# MD2020_02-08.net
KiCad netlist of a schematic drawn in EAGLE
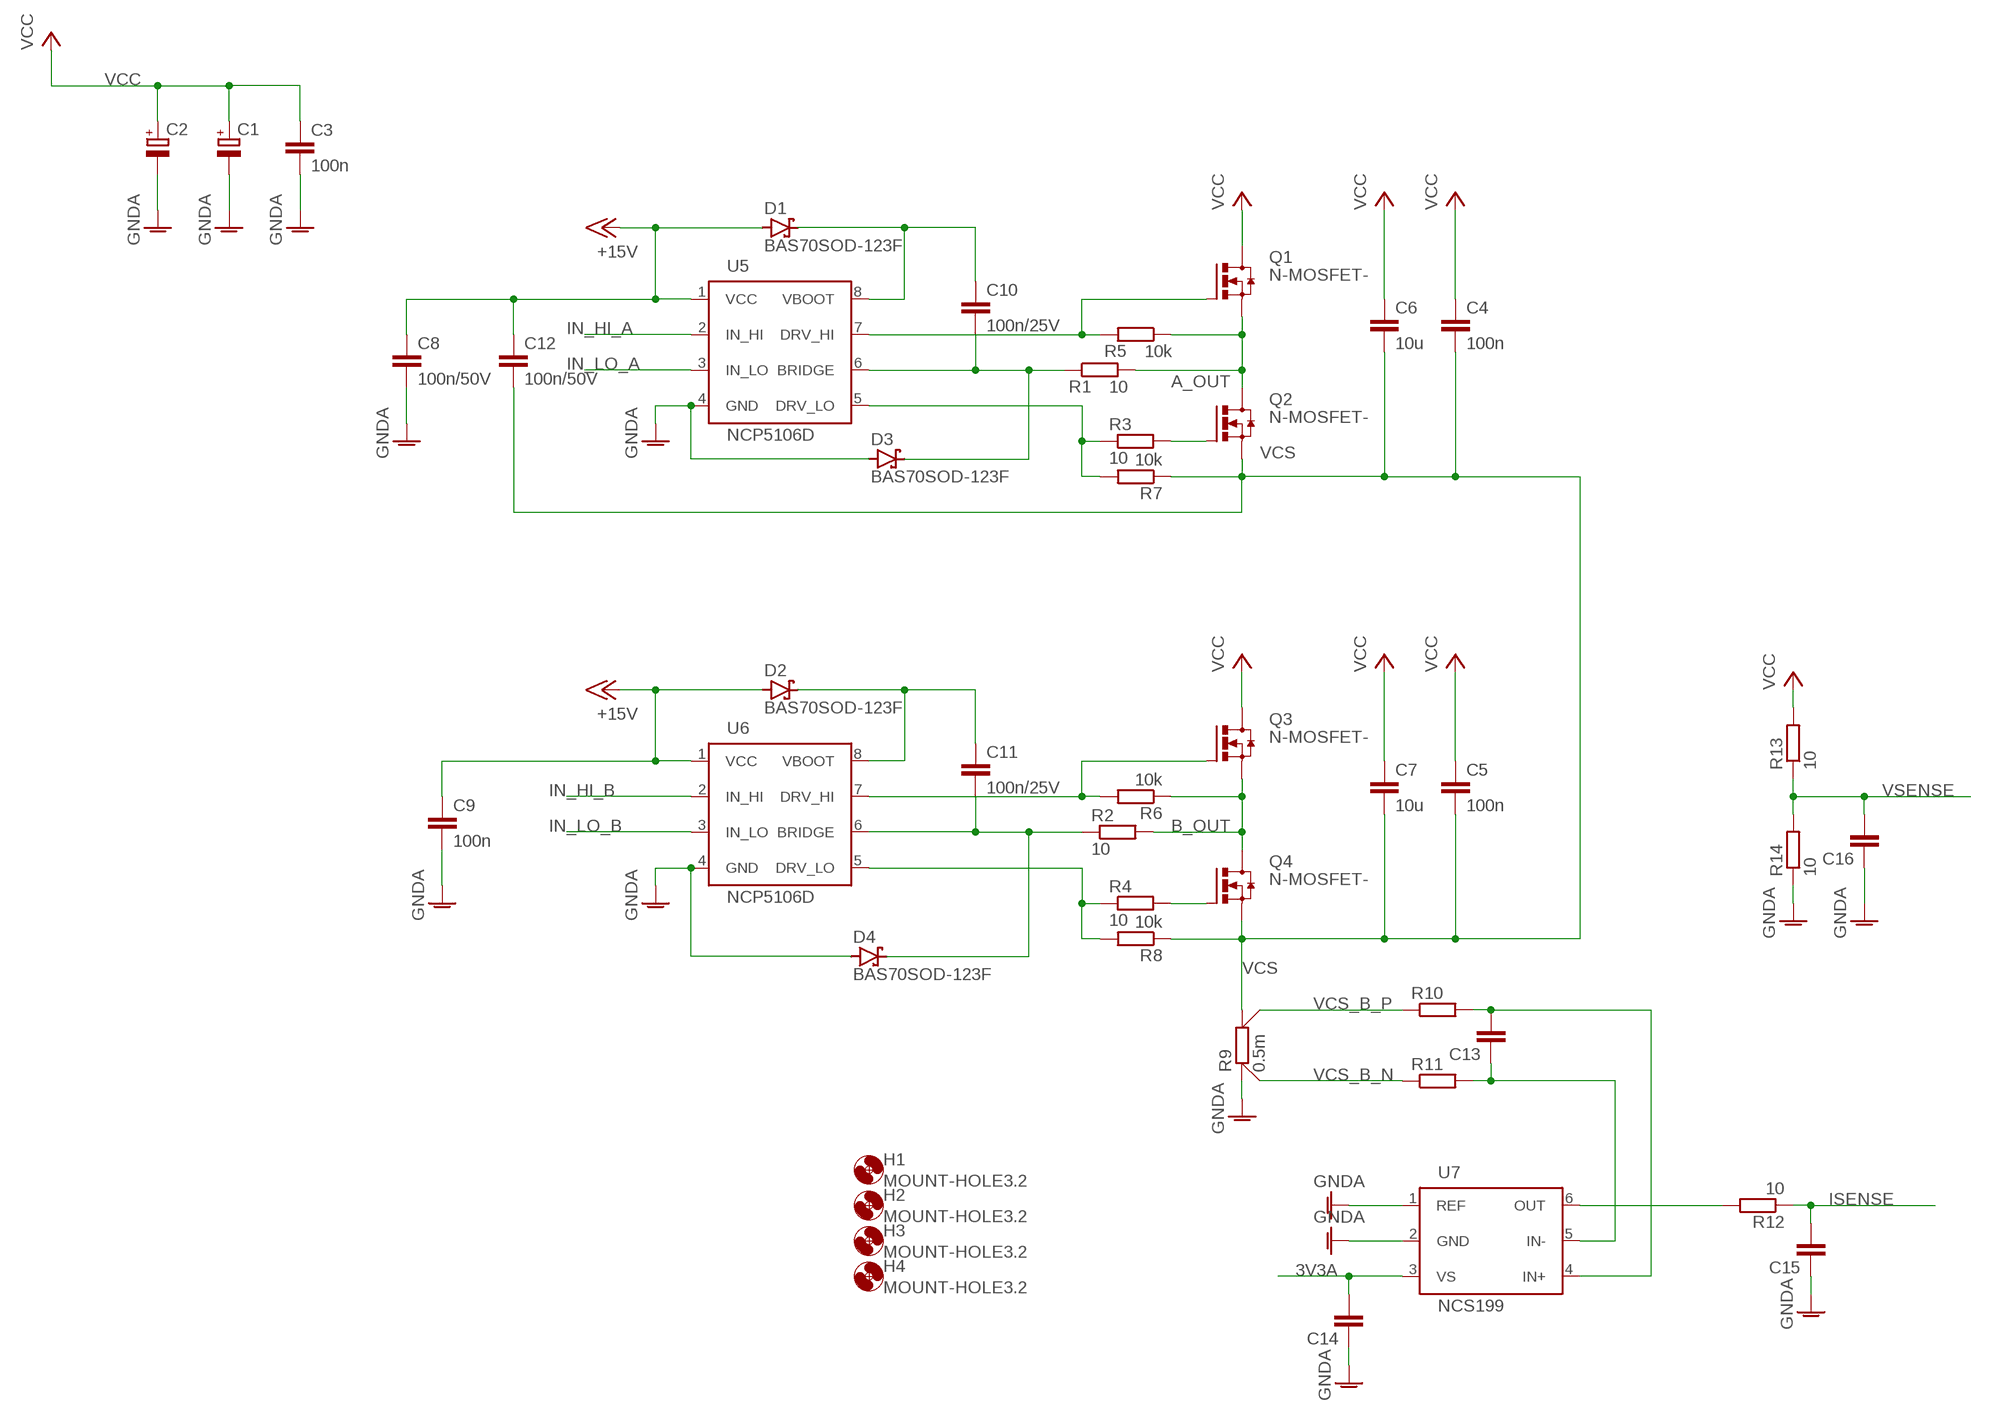
[diagram p0: schematic, sheet 1]
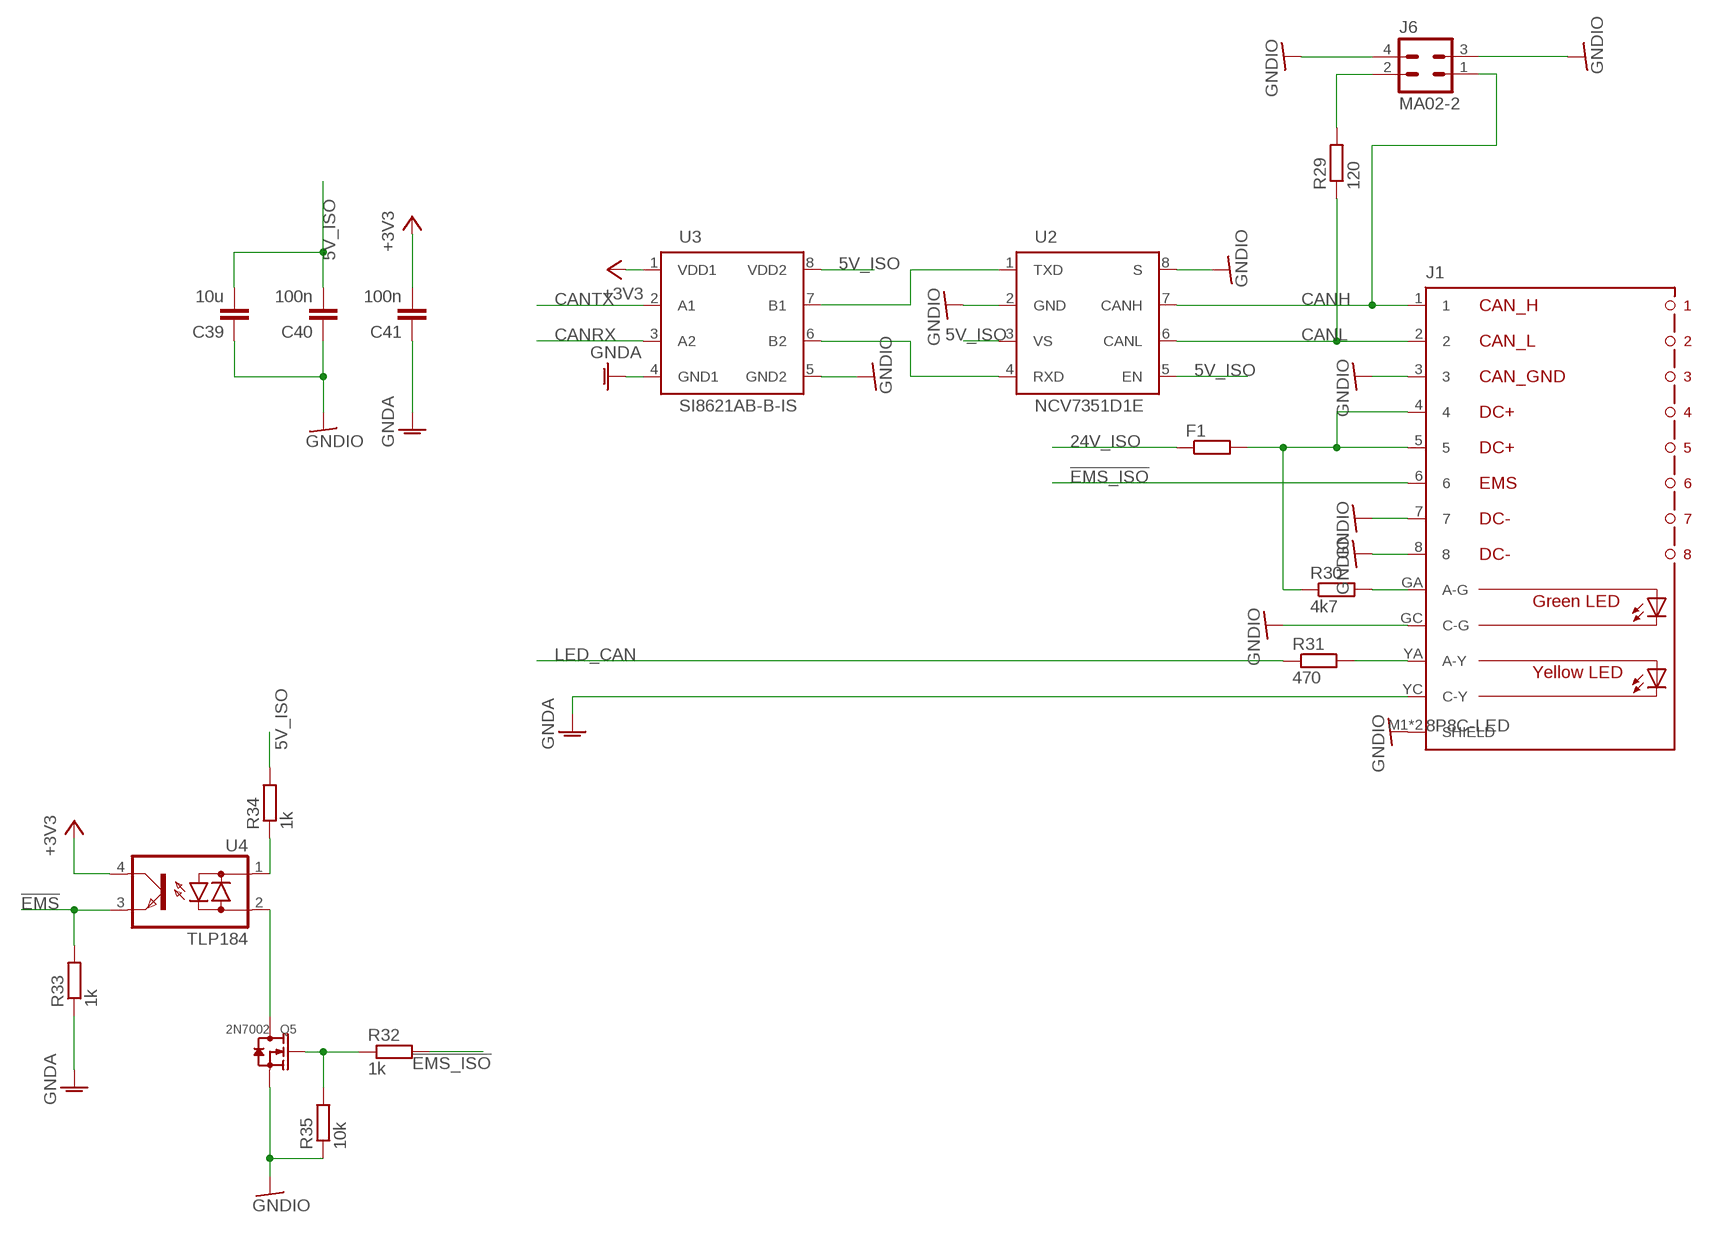
[diagram p1: schematic, sheet 2]
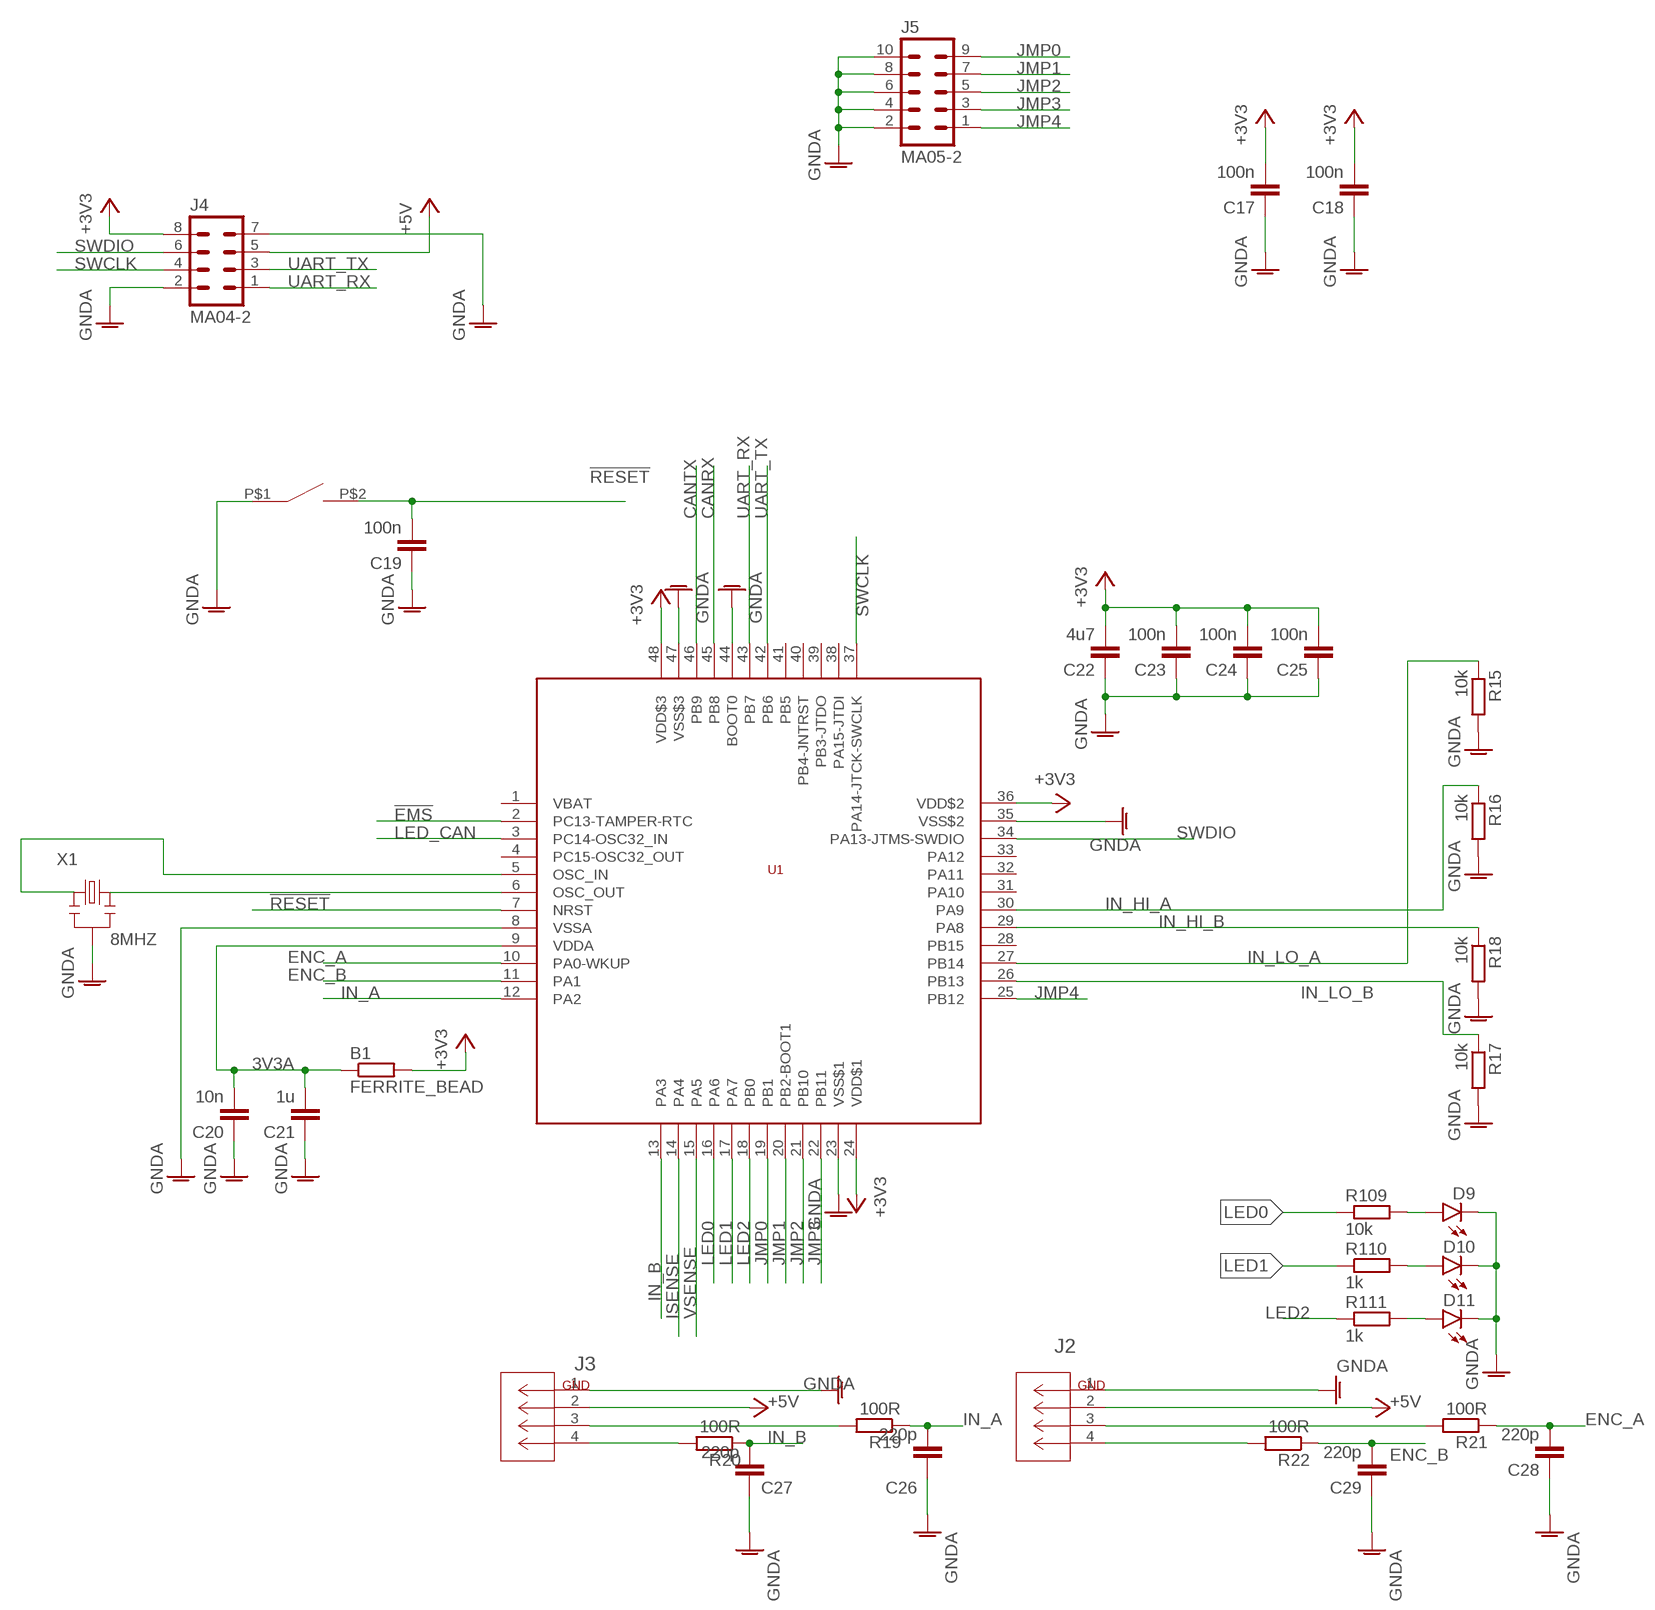
[diagram p2: schematic, sheet 3]
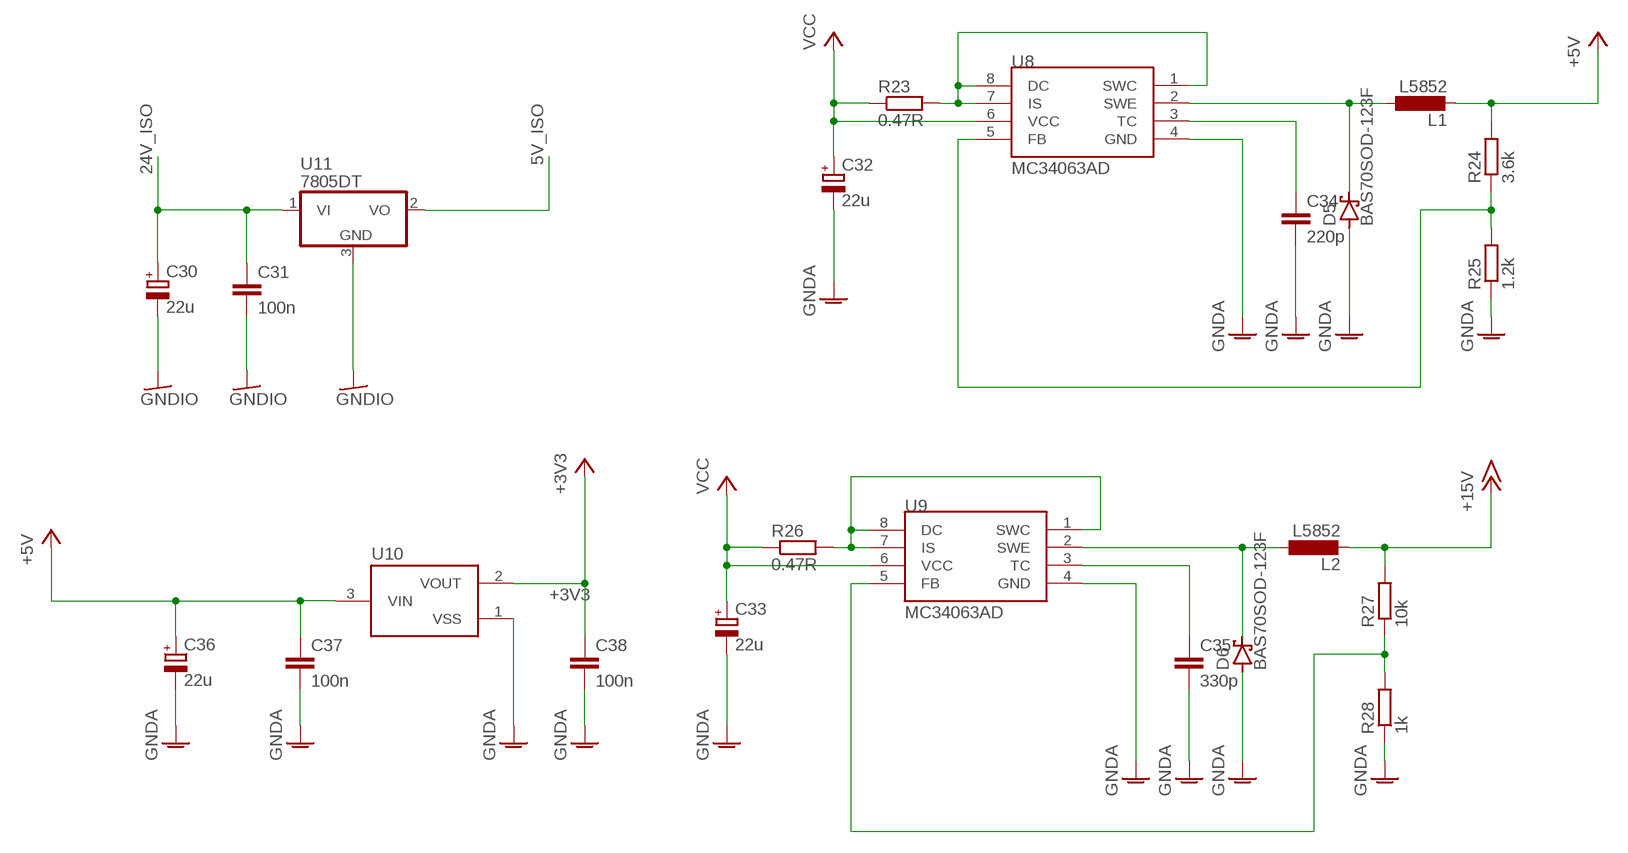
[diagram p3: schematic, sheet 4]

(export (version "E")
  (design (tool "Eeschema 10.0.6"))
  (components
    (comp (ref "C1")
      (value "CPOL-EUE5-10.5")
      (footprint "eagle-import:E5-10,5")
      (libsource (lib "eagle-import") (part "CPOL-EUE5-10.5"))
    )
    (comp (ref "C2")
      (value "CPOL-EUE5-10.5")
      (footprint "eagle-import:E5-10,5")
      (libsource (lib "eagle-import") (part "CPOL-EUE5-10.5"))
    )
    (comp (ref "C3")
      (value "100n")
      (footprint "eagle-import:C0603")
      (fields (field (name "MPN") "CC0603KRX7R9BB104 "))
      (libsource (lib "eagle-import") (part "C-EUC0603"))
    )
    (comp (ref "C4")
      (value "100n")
      (footprint "eagle-import:C0603")
      (fields (field (name "MPN") "CC0603KRX7R9BB104 "))
      (libsource (lib "eagle-import") (part "C-EUC0603"))
    )
    (comp (ref "C5")
      (value "100n")
      (footprint "eagle-import:C0603")
      (fields (field (name "MPN") "CC0603KRX7R9BB104 "))
      (libsource (lib "eagle-import") (part "C-EUC0603"))
    )
    (comp (ref "C6")
      (value "10u")
      (footprint "eagle-import:C1210")
      (fields (field (name "MPN") "CL31A106KBHNNNE "))
      (libsource (lib "eagle-import") (part "C-EUC1210"))
    )
    (comp (ref "C7")
      (value "10u")
      (footprint "eagle-import:C1210")
      (fields (field (name "MPN") "CL31A106KBHNNNE "))
      (libsource (lib "eagle-import") (part "C-EUC1210"))
    )
    (comp (ref "C8")
      (value "100n/50V")
      (footprint "eagle-import:C0603")
      (fields (field (name "MPN") "CC0603KRX7R9BB104 "))
      (libsource (lib "eagle-import") (part "C-EUC0603"))
    )
    (comp (ref "C9")
      (value "100n")
      (footprint "eagle-import:C0603")
      (fields (field (name "MPN") "CC0603KRX7R9BB104 "))
      (libsource (lib "eagle-import") (part "C-EUC0603"))
    )
    (comp (ref "C10")
      (value "100n/25V")
      (footprint "eagle-import:C0603")
      (fields (field (name "MPN") "CC0603KRX7R9BB104 "))
      (libsource (lib "eagle-import") (part "C-EUC0603"))
    )
    (comp (ref "C11")
      (value "100n/25V")
      (footprint "eagle-import:C0603")
      (fields (field (name "MPN") "CC0603KRX7R9BB104 "))
      (libsource (lib "eagle-import") (part "C-EUC0603"))
    )
    (comp (ref "C12")
      (value "100n/50V")
      (footprint "eagle-import:C0603")
      (fields (field (name "MPN") "CC0603KRX7R9BB104 "))
      (libsource (lib "eagle-import") (part "C-EUC0603"))
    )
    (comp (ref "C13")
      (value "C-EUC0603")
      (footprint "eagle-import:C0603")
      (libsource (lib "eagle-import") (part "rcl_334_C-EUC0603"))
    )
    (comp (ref "C14")
      (value "C-EUC0603")
      (footprint "eagle-import:C0603")
      (libsource (lib "eagle-import") (part "rcl_334_C-EUC0603"))
    )
    (comp (ref "C15")
      (value "C-EUC0603")
      (footprint "eagle-import:C0603")
      (libsource (lib "eagle-import") (part "rcl_334_C-EUC0603"))
    )
    (comp (ref "C16")
      (value "C-EUC0603")
      (footprint "eagle-import:C0603")
      (libsource (lib "eagle-import") (part "rcl_334_C-EUC0603"))
    )
    (comp (ref "D1")
      (value "BAS70SOD-123F")
      (footprint "eagle-import:SOD123F")
      (fields (field (name "MPN") "PMEG4010EH,115"))
      (libsource (lib "eagle-import") (part "BAS70SOD-123F"))
    )
    (comp (ref "D2")
      (value "BAS70SOD-123F")
      (footprint "eagle-import:SOD123F")
      (fields (field (name "MPN") "PMEG4010EH,115"))
      (libsource (lib "eagle-import") (part "BAS70SOD-123F"))
    )
    (comp (ref "D3")
      (value "BAS70SOD-123F")
      (footprint "eagle-import:SOD123F")
      (fields (field (name "MPN") "PMEG4010EH,115"))
      (libsource (lib "eagle-import") (part "BAS70SOD-123F"))
    )
    (comp (ref "D4")
      (value "BAS70SOD-123F")
      (footprint "eagle-import:SOD123F")
      (fields (field (name "MPN") "PMEG4010EH,115"))
      (libsource (lib "eagle-import") (part "BAS70SOD-123F"))
    )
    (comp (ref "H1")
      (value "MOUNT-HOLE3.2")
      (footprint "eagle-import:3,2")
      (libsource (lib "eagle-import") (part "MOUNT-HOLE3.2"))
    )
    (comp (ref "H2")
      (value "MOUNT-HOLE3.2")
      (footprint "eagle-import:3,2")
      (libsource (lib "eagle-import") (part "MOUNT-HOLE3.2"))
    )
    (comp (ref "H3")
      (value "MOUNT-HOLE3.2")
      (footprint "eagle-import:3,2")
      (libsource (lib "eagle-import") (part "MOUNT-HOLE3.2"))
    )
    (comp (ref "H4")
      (value "MOUNT-HOLE3.2")
      (footprint "eagle-import:3,2")
      (libsource (lib "eagle-import") (part "MOUNT-HOLE3.2"))
    )
    (comp (ref "Q1")
      (value "N-MOSFET-")
      (footprint "eagle-import:SOT669")
      (libsource (lib "eagle-import") (part "N-MOSFET-"))
    )
    (comp (ref "Q2")
      (value "N-MOSFET-")
      (footprint "eagle-import:SOT669")
      (libsource (lib "eagle-import") (part "N-MOSFET-"))
    )
    (comp (ref "Q3")
      (value "N-MOSFET-")
      (footprint "eagle-import:SOT669")
      (libsource (lib "eagle-import") (part "N-MOSFET-"))
    )
    (comp (ref "Q4")
      (value "N-MOSFET-")
      (footprint "eagle-import:SOT669")
      (libsource (lib "eagle-import") (part "N-MOSFET-"))
    )
    (comp (ref "R1")
      (value "10")
      (footprint "eagle-import:R0603")
      (fields (field (name "MPN") "RC0603FR-0710RL"))
      (libsource (lib "eagle-import") (part "R-EU_R0603"))
    )
    (comp (ref "R2")
      (value "10")
      (footprint "eagle-import:R0603")
      (fields (field (name "MPN") "RC0603FR-0710RL"))
      (libsource (lib "eagle-import") (part "R-EU_R0603"))
    )
    (comp (ref "R3")
      (value "10")
      (footprint "eagle-import:R0603")
      (fields (field (name "MPN") "RC0603FR-0710RL"))
      (libsource (lib "eagle-import") (part "R-EU_R0603"))
    )
    (comp (ref "R4")
      (value "10")
      (footprint "eagle-import:R0603")
      (fields (field (name "MPN") "RC0603FR-0710RL"))
      (libsource (lib "eagle-import") (part "R-EU_R0603"))
    )
    (comp (ref "R5")
      (value "10k")
      (footprint "eagle-import:R0603")
      (fields (field (name "MPN") "RC0603FR-0710KL "))
      (libsource (lib "eagle-import") (part "R-EU_R0603"))
    )
    (comp (ref "R6")
      (value "10k")
      (footprint "eagle-import:R0603")
      (fields (field (name "MPN") "RC0603FR-0710KL "))
      (libsource (lib "eagle-import") (part "R-EU_R0603"))
    )
    (comp (ref "R7")
      (value "10k")
      (footprint "eagle-import:R0603")
      (fields (field (name "MPN") "RC0603FR-0710KL "))
      (libsource (lib "eagle-import") (part "R-EU_R0603"))
    )
    (comp (ref "R8")
      (value "10k")
      (footprint "eagle-import:R0603")
      (fields (field (name "MPN") "RC0603FR-0710KL "))
      (libsource (lib "eagle-import") (part "R-EU_R0603"))
    )
    (comp (ref "R9")
      (value "0.5m")
      (footprint "eagle-import:CSS2H-2512")
      (libsource (lib "eagle-import") (part "CSS2H-2512"))
    )
    (comp (ref "R10")
      (value "R-EU_R0603")
      (footprint "eagle-import:R0603")
      (libsource (lib "eagle-import") (part "rcl_334_R-EU_R0603"))
    )
    (comp (ref "R11")
      (value "R-EU_R0603")
      (footprint "eagle-import:R0603")
      (libsource (lib "eagle-import") (part "rcl_334_R-EU_R0603"))
    )
    (comp (ref "R12")
      (value "10")
      (footprint "eagle-import:R0603")
      (fields (field (name "MPN") "RC0603FR-0710RL"))
      (libsource (lib "eagle-import") (part "R-EU_R0603"))
    )
    (comp (ref "R13")
      (value "10")
      (footprint "eagle-import:R0603")
      (fields (field (name "MPN") "RC0603FR-0710RL"))
      (libsource (lib "eagle-import") (part "R-EU_R0603"))
    )
    (comp (ref "R14")
      (value "10")
      (footprint "eagle-import:R0603")
      (fields (field (name "MPN") "RC0603FR-0710RL"))
      (libsource (lib "eagle-import") (part "R-EU_R0603"))
    )
    (comp (ref "U5")
      (value "NCP5106D")
      (footprint "eagle-import:SOIC127P600X175-8")
      (libsource (lib "eagle-import") (part "NCP5106D"))
    )
    (comp (ref "U6")
      (value "NCP5106D")
      (footprint "eagle-import:SOIC127P600X175-8")
      (libsource (lib "eagle-import") (part "NCP5106D"))
    )
    (comp (ref "U7")
      (value "NCS199")
      (footprint "eagle-import:SOT65P210X110-6")
      (libsource (lib "eagle-import") (part "NCS199"))
    )
    (comp (ref "C39")
      (value "10u")
      (footprint "eagle-import:C0805")
      (fields (field (name "MPN") "CC0805ZKY5V6BB106 "))
      (libsource (lib "eagle-import") (part "C-EUC0805"))
    )
    (comp (ref "C40")
      (value "100n")
      (footprint "eagle-import:C0603")
      (fields (field (name "MPN") "CC0603KRX7R9BB104 "))
      (libsource (lib "eagle-import") (part "C-EUC0603"))
    )
    (comp (ref "C41")
      (value "100n")
      (footprint "eagle-import:C0603")
      (fields (field (name "MPN") "CC0603KRX7R9BB104 "))
      (libsource (lib "eagle-import") (part "C-EUC0603"))
    )
    (comp (ref "F1")
      (value "R-EU_R1206")
      (footprint "eagle-import:R1206")
      (libsource (lib "eagle-import") (part "rcl_334_R-EU_R1206"))
    )
    (comp (ref "J1")
      (value "8P8C-LED")
      (footprint "eagle-import:8P8C-LED")
      (libsource (lib "eagle-import") (part "8P8C-LED"))
    )
    (comp (ref "J6")
      (value "MA02-2")
      (footprint "eagle-import:MA02-2W")
      (libsource (lib "eagle-import") (part "MA02-2"))
    )
    (comp (ref "Q5")
      (value "2N7002")
      (footprint "eagle-import:SOT-23")
      (fields (field (name "MPN") "2N7002,215"))
      (libsource (lib "eagle-import") (part "SMD-MOSFET-N-CH-60V-300MA-LOGIC-LEVEL-FET-2N7002(SOT-23)"))
    )
    (comp (ref "R29")
      (value "120")
      (footprint "eagle-import:R0603")
      (fields (field (name "MPN") "RC0603JR-07120RL "))
      (libsource (lib "eagle-import") (part "rcl_334_R-EU_R0603"))
    )
    (comp (ref "R30")
      (value "4k7")
      (footprint "eagle-import:R0603")
      (fields (field (name "MPN") "RC0603FR-074K7L "))
      (libsource (lib "eagle-import") (part "rcl_334_R-EU_R0603"))
    )
    (comp (ref "R31")
      (value "470")
      (footprint "eagle-import:R0603")
      (fields (field (name "MPN") "RC0603JR-07470RL "))
      (libsource (lib "eagle-import") (part "rcl_334_R-EU_R0603"))
    )
    (comp (ref "R32")
      (value "1k")
      (footprint "eagle-import:R0603")
      (fields (field (name "MPN") "RC0603FR-071KL "))
      (libsource (lib "eagle-import") (part "rcl_334_R-EU_R0603"))
    )
    (comp (ref "R33")
      (value "1k")
      (footprint "eagle-import:R0603")
      (fields (field (name "MPN") "RC0603FR-071KL "))
      (libsource (lib "eagle-import") (part "rcl_334_R-EU_R0603"))
    )
    (comp (ref "R34")
      (value "1k")
      (footprint "eagle-import:R0603")
      (fields (field (name "MPN") "RC0603FR-071KL "))
      (libsource (lib "eagle-import") (part "rcl_334_R-EU_R0603"))
    )
    (comp (ref "R35")
      (value "10k")
      (footprint "eagle-import:R0603")
      (fields (field (name "MPN") "RC0603FR-0710KL "))
      (libsource (lib "eagle-import") (part "rcl_334_R-EU_R0603"))
    )
    (comp (ref "U2")
      (value "NCV7351D1E")
      (footprint "eagle-import:SO08")
      (libsource (lib "eagle-import") (part "NCV7351D1E"))
    )
    (comp (ref "U3")
      (value "SI8621AB-B-IS")
      (footprint "eagle-import:SO08")
      (libsource (lib "eagle-import") (part "SI8621AB-B-IS"))
    )
    (comp (ref "U4")
      (value "TLP184")
      (footprint "eagle-import:11-4M1S")
      (libsource (lib "eagle-import") (part "TLP184"))
    )
    (comp (ref "C30")
      (value "22u")
      (footprint "eagle-import:E2,5-5")
      (libsource (lib "eagle-import") (part "CPOL-EUE2.5-5"))
    )
    (comp (ref "C31")
      (value "100n")
      (footprint "eagle-import:C0603")
      (fields (field (name "MPN") "CC0603KRX7R9BB104 "))
      (libsource (lib "eagle-import") (part "C-EUC0603"))
    )
    (comp (ref "C32")
      (value "22u")
      (footprint "eagle-import:E2-5")
      (libsource (lib "eagle-import") (part "CPOL-EUE2-5"))
    )
    (comp (ref "C33")
      (value "22u")
      (footprint "eagle-import:E2-5")
      (libsource (lib "eagle-import") (part "CPOL-EUE2-5"))
    )
    (comp (ref "C34")
      (value "220p")
      (footprint "eagle-import:C0603")
      (fields (field (name "MPN") "CL10B221KB8NNNC "))
      (libsource (lib "eagle-import") (part "rcl_334_C-EUC0603"))
    )
    (comp (ref "C35")
      (value "330p")
      (footprint "eagle-import:C0603")
      (fields (field (name "MPN") "CL10B331KB8NNNC "))
      (libsource (lib "eagle-import") (part "rcl_334_C-EUC0603"))
    )
    (comp (ref "C36")
      (value "22u")
      (footprint "eagle-import:E2,5-5")
      (libsource (lib "eagle-import") (part "CPOL-EUE2.5-5"))
    )
    (comp (ref "C37")
      (value "100n")
      (footprint "eagle-import:C0603")
      (fields (field (name "MPN") "CC0603KRX7R9BB104 "))
      (libsource (lib "eagle-import") (part "C-EUC0603"))
    )
    (comp (ref "C38")
      (value "100n")
      (footprint "eagle-import:C0603")
      (fields (field (name "MPN") "CC0603KRX7R9BB104 "))
      (libsource (lib "eagle-import") (part "C-EUC0603"))
    )
    (comp (ref "D5")
      (value "BAS70SOD-123F")
      (footprint "eagle-import:SOD123F")
      (fields (field (name "MPN") "PMEG4010EH,115"))
      (libsource (lib "eagle-import") (part "BAS70SOD-123F"))
    )
    (comp (ref "D6")
      (value "BAS70SOD-123F")
      (footprint "eagle-import:SOD123F")
      (fields (field (name "MPN") "PMEG4010EH,115"))
      (libsource (lib "eagle-import") (part "BAS70SOD-123F"))
    )
    (comp (ref "L1")
      (value "L5852")
      (footprint "eagle-import:L5852")
      (libsource (lib "eagle-import") (part "L5852"))
    )
    (comp (ref "L2")
      (value "L5852")
      (footprint "eagle-import:L5852")
      (libsource (lib "eagle-import") (part "L5852"))
    )
    (comp (ref "R23")
      (value "0.47R")
      (footprint "eagle-import:R0603")
      (fields (field (name "MPN") "0603WAF470LT5E "))
      (libsource (lib "eagle-import") (part "rcl_334_R-EU_R0603"))
    )
    (comp (ref "R24")
      (value "3.6k")
      (footprint "eagle-import:R0603")
      (fields (field (name "MPN") "RC0603JR-073K6L "))
      (libsource (lib "eagle-import") (part "rcl_334_R-EU_R0603"))
    )
    (comp (ref "R25")
      (value "1.2k")
      (footprint "eagle-import:R0603")
      (fields (field (name "MPN") "RC0603JR-071K2L "))
      (libsource (lib "eagle-import") (part "rcl_334_R-EU_R0603"))
    )
    (comp (ref "R26")
      (value "0.47R")
      (footprint "eagle-import:R0603")
      (fields (field (name "MPN") "0603WAF470LT5E "))
      (libsource (lib "eagle-import") (part "rcl_334_R-EU_R0603"))
    )
    (comp (ref "R27")
      (value "10k")
      (footprint "eagle-import:R0603")
      (fields (field (name "MPN") "RC0603FR-0710KL "))
      (libsource (lib "eagle-import") (part "rcl_334_R-EU_R0603"))
    )
    (comp (ref "R28")
      (value "1k")
      (footprint "eagle-import:R0603")
      (fields (field (name "MPN") "RC0603FR-071KL "))
      (libsource (lib "eagle-import") (part "rcl_334_R-EU_R0603"))
    )
    (comp (ref "U8")
      (value "MC34063AD")
      (footprint "eagle-import:SOIC8")
      (fields (field (name "MPN") "MC34063ADR2G "))
      (libsource (lib "eagle-import") (part "MC34063AD"))
    )
    (comp (ref "U9")
      (value "MC34063AD")
      (footprint "eagle-import:SOIC8")
      (fields (field (name "MPN") "MC34063ADR2G "))
      (libsource (lib "eagle-import") (part "MC34063AD"))
    )
    (comp (ref "U10")
      (value "XC6206")
      (footprint "eagle-import:SOT95P240X110-3")
      (libsource (lib "eagle-import") (part "XC6206"))
    )
    (comp (ref "U11")
      (value "7805DT")
      (footprint "eagle-import:TO252")
      (libsource (lib "eagle-import") (part "78DT05"))
    )
    (comp (ref "B1")
      (value "FERRITE_BEAD")
      (footprint "eagle-import:R0603")
      (libsource (lib "eagle-import") (part "R-EU_R0603"))
    )
    (comp (ref "C17")
      (value "100n")
      (footprint "eagle-import:C0603")
      (fields (field (name "MPN") "CC0603KRX7R9BB104 "))
      (libsource (lib "eagle-import") (part "C-EUC0603"))
    )
    (comp (ref "C18")
      (value "100n")
      (footprint "eagle-import:C0603")
      (fields (field (name "MPN") "CC0603KRX7R9BB104 "))
      (libsource (lib "eagle-import") (part "C-EUC0603"))
    )
    (comp (ref "C19")
      (value "100n")
      (footprint "eagle-import:C0603")
      (fields (field (name "MPN") "CC0603KRX7R9BB104 "))
      (libsource (lib "eagle-import") (part "C-EUC0603"))
    )
    (comp (ref "C20")
      (value "10n")
      (footprint "eagle-import:C0603")
      (libsource (lib "eagle-import") (part "C-EUC0603"))
    )
    (comp (ref "C21")
      (value "1u")
      (footprint "eagle-import:C0603")
      (fields (field (name "MPN") "CC0603KRX7R8BB105 "))
      (libsource (lib "eagle-import") (part "C-EUC0603"))
    )
    (comp (ref "C22")
      (value "4u7")
      (footprint "eagle-import:C0805")
      (fields (field (name "MPN") "CC0603KRX5R6BB475 "))
      (libsource (lib "eagle-import") (part "C-EUC0805"))
    )
    (comp (ref "C23")
      (value "100n")
      (footprint "eagle-import:C0603")
      (fields (field (name "MPN") "CC0603KRX7R9BB104 "))
      (libsource (lib "eagle-import") (part "C-EUC0603"))
    )
    (comp (ref "C24")
      (value "100n")
      (footprint "eagle-import:C0603")
      (fields (field (name "MPN") "CC0603KRX7R9BB104 "))
      (libsource (lib "eagle-import") (part "C-EUC0603"))
    )
    (comp (ref "C25")
      (value "100n")
      (footprint "eagle-import:C0603")
      (fields (field (name "MPN") "CC0603KRX7R9BB104 "))
      (libsource (lib "eagle-import") (part "C-EUC0603"))
    )
    (comp (ref "C26")
      (value "220p")
      (footprint "eagle-import:C0603")
      (fields (field (name "MPN") "CL10B221KB8NNNC "))
      (libsource (lib "eagle-import") (part "C-EUC0603"))
    )
    (comp (ref "C27")
      (value "220p")
      (footprint "eagle-import:C0603")
      (fields (field (name "MPN") "CL10B221KB8NNNC "))
      (libsource (lib "eagle-import") (part "C-EUC0603"))
    )
    (comp (ref "C28")
      (value "220p")
      (footprint "eagle-import:C0603")
      (fields (field (name "MPN") "CL10B221KB8NNNC "))
      (libsource (lib "eagle-import") (part "C-EUC0603"))
    )
    (comp (ref "C29")
      (value "220p")
      (footprint "eagle-import:C0603")
      (fields (field (name "MPN") "CL10B221KB8NNNC "))
      (libsource (lib "eagle-import") (part "C-EUC0603"))
    )
    (comp (ref "D9")
      (value "LEDCHIPLED_0805")
      (footprint "eagle-import:CHIPLED_0805")
      (libsource (lib "eagle-import") (part "LEDCHIPLED_0805"))
    )
    (comp (ref "D10")
      (value "LEDCHIPLED_0805")
      (footprint "eagle-import:CHIPLED_0805")
      (libsource (lib "eagle-import") (part "LEDCHIPLED_0805"))
    )
    (comp (ref "D11")
      (value "LEDCHIPLED_0805")
      (footprint "eagle-import:CHIPLED_0805")
      (libsource (lib "eagle-import") (part "LEDCHIPLED_0805"))
    )
    (comp (ref "J2")
      (value "1744426-4")
      (footprint "eagle-import:CONN4_1744426-4")
      (fields (field (name "MANUFACTURER_PART_NUMBER") "17444264"))
      (libsource (lib "eagle-import") (part "1744426-4"))
    )
    (comp (ref "J3")
      (value "1744426-4")
      (footprint "eagle-import:CONN4_1744426-4")
      (fields (field (name "MANUFACTURER_PART_NUMBER") "17444264"))
      (libsource (lib "eagle-import") (part "1744426-4"))
    )
    (comp (ref "J4")
      (value "MA04-2")
      (footprint "eagle-import:MA04-2W")
      (libsource (lib "eagle-import") (part "MA04-2"))
    )
    (comp (ref "J5")
      (value "MA05-2")
      (footprint "eagle-import:MA05-2W")
      (libsource (lib "eagle-import") (part "MA05-2"))
    )
    (comp (ref "R15")
      (value "10k")
      (footprint "eagle-import:R0603")
      (fields (field (name "MPN") "RC0603FR-0710KL "))
      (libsource (lib "eagle-import") (part "R-EU_R0603"))
    )
    (comp (ref "R16")
      (value "10k")
      (footprint "eagle-import:R0603")
      (fields (field (name "MPN") "RC0603FR-0710KL "))
      (libsource (lib "eagle-import") (part "R-EU_R0603"))
    )
    (comp (ref "R17")
      (value "10k")
      (footprint "eagle-import:R0603")
      (fields (field (name "MPN") "RC0603FR-0710KL "))
      (libsource (lib "eagle-import") (part "R-EU_R0603"))
    )
    (comp (ref "R18")
      (value "10k")
      (footprint "eagle-import:R0603")
      (fields (field (name "MPN") "RC0603FR-0710KL "))
      (libsource (lib "eagle-import") (part "R-EU_R0603"))
    )
    (comp (ref "R19")
      (value "100R")
      (footprint "eagle-import:R0603")
      (fields (field (name "MPN") "RC0603JR-07100RL "))
      (libsource (lib "eagle-import") (part "R-EU_R0603"))
    )
    (comp (ref "R20")
      (value "100R")
      (footprint "eagle-import:R0603")
      (fields (field (name "MPN") "RC0603JR-07100RL "))
      (libsource (lib "eagle-import") (part "R-EU_R0603"))
    )
    (comp (ref "R21")
      (value "100R")
      (footprint "eagle-import:R0603")
      (fields (field (name "MPN") "RC0603JR-07100RL "))
      (libsource (lib "eagle-import") (part "R-EU_R0603"))
    )
    (comp (ref "R22")
      (value "100R")
      (footprint "eagle-import:R0603")
      (fields (field (name "MPN") "RC0603JR-07100RL "))
      (libsource (lib "eagle-import") (part "R-EU_R0603"))
    )
    (comp (ref "R109")
      (value "10k")
      (footprint "eagle-import:R0603")
      (fields (field (name "MPN") "RC0603FR-0710KL "))
      (libsource (lib "eagle-import") (part "R-EU_R0603"))
    )
    (comp (ref "R110")
      (value "1k")
      (footprint "eagle-import:R0603")
      (fields (field (name "MPN") "RC0603FR-071KL "))
      (libsource (lib "eagle-import") (part "R-EU_R0603"))
    )
    (comp (ref "R111")
      (value "1k")
      (footprint "eagle-import:R0603")
      (fields (field (name "MPN") "RC0603FR-071KL "))
      (libsource (lib "eagle-import") (part "R-EU_R0603"))
    )
    (comp (ref "S1")
      (value "SWITCH_TACTILETOP")
      (footprint "eagle-import:SWITCH_TACTILE_3X6")
      (libsource (lib "eagle-import") (part "SWITCH_TACTILETOP"))
    )
    (comp (ref "U1")
      (value "STM32F103C8")
      (footprint "eagle-import:LQFP48")
      (fields (field (name "MPN") "STM32F103C8T6 "))
      (libsource (lib "eagle-import") (part "STM32F103C8"))
    )
    (comp (ref "X1")
      (value "8MHZ")
      (footprint "eagle-import:X3-SMD-3.6X1.3X0.8MM")
      (fields (field (name "MPN") "CSTCE8M00G55-RO "))
      (libsource (lib "eagle-import") (part "SMD-CRYSTAL-8MHZ--0.3%-150R(3P-3.6X1.3MM)"))
    )
  )
  (nets
    (net (code "1") (name "+3V3") (class "Default")
      (node (ref "B1") (pin "2") (pinfunction "2_2") (pintype "passive"))
      (node (ref "C17") (pin "2") (pinfunction "2_2") (pintype "passive"))
      (node (ref "C18") (pin "2") (pinfunction "2_2") (pintype "passive"))
      (node (ref "C22") (pin "2") (pinfunction "2_2") (pintype "passive"))
      (node (ref "C23") (pin "2") (pinfunction "2_2") (pintype "passive"))
      (node (ref "C24") (pin "2") (pinfunction "2_2") (pintype "passive"))
      (node (ref "C25") (pin "2") (pinfunction "2_2") (pintype "passive"))
      (node (ref "C38") (pin "1") (pinfunction "1_1") (pintype "passive"))
      (node (ref "C41") (pin "2") (pinfunction "2_2") (pintype "passive"))
      (node (ref "J4") (pin "8") (pinfunction "8_8") (pintype "passive"))
      (node (ref "U1") (pin "24") (pinfunction "VDD$1_24") (pintype "passive"))
      (node (ref "U1") (pin "36") (pinfunction "VDD$2_36") (pintype "passive"))
      (node (ref "U1") (pin "48") (pinfunction "VDD$3_48") (pintype "passive"))
      (node (ref "U10") (pin "2") (pinfunction "VOUT_2") (pintype "bidirectional"))
      (node (ref "U3") (pin "1") (pinfunction "VDD1_1") (pintype "power_in"))
      (node (ref "U4") (pin "4") (pinfunction "C_4") (pintype "passive"))
    )
    (net (code "2") (name "+5V") (class "Default")
      (node (ref "C36") (pin "+") (pinfunction "+_+") (pintype "passive"))
      (node (ref "C37") (pin "1") (pinfunction "1_1") (pintype "passive"))
      (node (ref "J2") (pin "2") (pinfunction "2_2") (pintype "passive"))
      (node (ref "J3") (pin "2") (pinfunction "2_2") (pintype "passive"))
      (node (ref "J4") (pin "5") (pinfunction "5_5") (pintype "passive"))
      (node (ref "L1") (pin "P$2") (pinfunction "2_P$2") (pintype "passive"))
      (node (ref "R24") (pin "2") (pinfunction "2_2") (pintype "passive"))
      (node (ref "U10") (pin "3") (pinfunction "VIN_3") (pintype "bidirectional"))
    )
    (net (code "3") (name "+15V") (class "Default")
      (node (ref "C12") (pin "1") (pinfunction "1_1") (pintype "passive"))
      (node (ref "C8") (pin "1") (pinfunction "1_1") (pintype "passive"))
      (node (ref "C9") (pin "1") (pinfunction "1_1") (pintype "passive"))
      (node (ref "D1") (pin "A") (pinfunction "A_A") (pintype "passive"))
      (node (ref "D2") (pin "A") (pinfunction "A_A") (pintype "passive"))
      (node (ref "L2") (pin "P$2") (pinfunction "2_P$2") (pintype "passive"))
      (node (ref "R27") (pin "2") (pinfunction "2_2") (pintype "passive"))
      (node (ref "U5") (pin "1") (pinfunction "VCC_1") (pintype "power_in"))
      (node (ref "U6") (pin "1") (pinfunction "VCC_1") (pintype "power_in"))
    )
    (net (code "4") (name "3V3A") (class "Default")
      (node (ref "B1") (pin "1") (pinfunction "1_1") (pintype "passive"))
      (node (ref "C14") (pin "2") (pinfunction "2_2") (pintype "passive"))
      (node (ref "C20") (pin "2") (pinfunction "2_2") (pintype "passive"))
      (node (ref "C21") (pin "2") (pinfunction "2_2") (pintype "passive"))
      (node (ref "U1") (pin "9") (pinfunction "VDDA_9") (pintype "bidirectional"))
      (node (ref "U7") (pin "3") (pinfunction "VS_3") (pintype "power_in"))
    )
    (net (code "5") (name "5V_ISO") (class "Default")
      (node (ref "C39") (pin "2") (pinfunction "2_2") (pintype "passive"))
      (node (ref "C40") (pin "2") (pinfunction "2_2") (pintype "passive"))
      (node (ref "R34") (pin "2") (pinfunction "2_2") (pintype "passive"))
      (node (ref "U11") (pin "2") (pinfunction "VO_2") (pintype "passive"))
      (node (ref "U2") (pin "3") (pinfunction "VS_3") (pintype "power_in"))
      (node (ref "U2") (pin "5") (pinfunction "EN_5") (pintype "input"))
      (node (ref "U3") (pin "8") (pinfunction "VDD2_8") (pintype "power_in"))
    )
    (net (code "6") (name "24V_ISO") (class "Default")
      (node (ref "C30") (pin "+") (pinfunction "+_+") (pintype "passive"))
      (node (ref "C31") (pin "1") (pinfunction "1_1") (pintype "passive"))
      (node (ref "F1") (pin "1") (pinfunction "1_1") (pintype "passive"))
      (node (ref "U11") (pin "1") (pinfunction "VI_1") (pintype "input"))
    )
    (net (code "7") (name "A_OUT") (class "Default")
      (node (ref "Q1") (pin "1") (pinfunction "SOURCE_1") (pintype "passive"))
      (node (ref "Q1") (pin "2") (pinfunction "SOURCE_2") (pintype "passive"))
      (node (ref "Q1") (pin "3") (pinfunction "SOURCE_3") (pintype "passive"))
      (node (ref "Q2") (pin "5") (pinfunction "DRAIN_5") (pintype "passive"))
      (node (ref "R1") (pin "2") (pinfunction "2_2") (pintype "passive"))
      (node (ref "R5") (pin "1") (pinfunction "1_1") (pintype "passive"))
    )
    (net (code "8") (name "B_OUT") (class "Default")
      (node (ref "Q3") (pin "1") (pinfunction "SOURCE_1") (pintype "passive"))
      (node (ref "Q3") (pin "2") (pinfunction "SOURCE_2") (pintype "passive"))
      (node (ref "Q3") (pin "3") (pinfunction "SOURCE_3") (pintype "passive"))
      (node (ref "Q4") (pin "5") (pinfunction "DRAIN_5") (pintype "passive"))
      (node (ref "R2") (pin "2") (pinfunction "2_2") (pintype "passive"))
      (node (ref "R6") (pin "1") (pinfunction "1_1") (pintype "passive"))
    )
    (net (code "9") (name "CANH") (class "Default")
      (node (ref "J1") (pin "1") (pinfunction "1_1") (pintype "input"))
      (node (ref "J6") (pin "1") (pinfunction "1_1") (pintype "passive"))
      (node (ref "U2") (pin "7") (pinfunction "CANH_7") (pintype "output"))
    )
    (net (code "10") (name "CANL") (class "Default")
      (node (ref "J1") (pin "2") (pinfunction "2_2") (pintype "input"))
      (node (ref "R29") (pin "1") (pinfunction "1_1") (pintype "passive"))
      (node (ref "U2") (pin "6") (pinfunction "CANL_6") (pintype "output"))
    )
    (net (code "11") (name "CANRX") (class "Default")
      (node (ref "U1") (pin "45") (pinfunction "PB8_45") (pintype "bidirectional"))
      (node (ref "U3") (pin "3") (pinfunction "A2_3") (pintype "output"))
    )
    (net (code "12") (name "CANTX") (class "Default")
      (node (ref "U1") (pin "46") (pinfunction "PB9_46") (pintype "bidirectional"))
      (node (ref "U3") (pin "2") (pinfunction "A1_2") (pintype "input"))
    )
    (net (code "13") (name "ENC_A") (class "Default")
      (node (ref "C28") (pin "2") (pinfunction "2_2") (pintype "passive"))
      (node (ref "R21") (pin "1") (pinfunction "1_1") (pintype "passive"))
      (node (ref "U1") (pin "10") (pinfunction "PA0-WKUP_10") (pintype "bidirectional"))
    )
    (net (code "14") (name "ENC_B") (class "Default")
      (node (ref "C29") (pin "2") (pinfunction "2_2") (pintype "passive"))
      (node (ref "R22") (pin "1") (pinfunction "1_1") (pintype "passive"))
      (node (ref "U1") (pin "11") (pinfunction "PA1_11") (pintype "bidirectional"))
    )
    (net (code "15") (name "GNDA") (class "Default")
      (node (ref "C1") (pin "-") (pinfunction "-_-") (pintype "passive"))
      (node (ref "C14") (pin "1") (pinfunction "1_1") (pintype "passive"))
      (node (ref "C15") (pin "1") (pinfunction "1_1") (pintype "passive"))
      (node (ref "C16") (pin "1") (pinfunction "1_1") (pintype "passive"))
      (node (ref "C17") (pin "1") (pinfunction "1_1") (pintype "passive"))
      (node (ref "C18") (pin "1") (pinfunction "1_1") (pintype "passive"))
      (node (ref "C19") (pin "1") (pinfunction "1_1") (pintype "passive"))
      (node (ref "C2") (pin "-") (pinfunction "-_-") (pintype "passive"))
      (node (ref "C20") (pin "1") (pinfunction "1_1") (pintype "passive"))
      (node (ref "C21") (pin "1") (pinfunction "1_1") (pintype "passive"))
      (node (ref "C22") (pin "1") (pinfunction "1_1") (pintype "passive"))
      (node (ref "C23") (pin "1") (pinfunction "1_1") (pintype "passive"))
      (node (ref "C24") (pin "1") (pinfunction "1_1") (pintype "passive"))
      (node (ref "C25") (pin "1") (pinfunction "1_1") (pintype "passive"))
      (node (ref "C26") (pin "1") (pinfunction "1_1") (pintype "passive"))
      (node (ref "C27") (pin "1") (pinfunction "1_1") (pintype "passive"))
      (node (ref "C28") (pin "1") (pinfunction "1_1") (pintype "passive"))
      (node (ref "C29") (pin "1") (pinfunction "1_1") (pintype "passive"))
      (node (ref "C3") (pin "2") (pinfunction "2_2") (pintype "passive"))
      (node (ref "C32") (pin "-") (pinfunction "-_-") (pintype "passive"))
      (node (ref "C33") (pin "-") (pinfunction "-_-") (pintype "passive"))
      (node (ref "C34") (pin "2") (pinfunction "2_2") (pintype "passive"))
      (node (ref "C35") (pin "2") (pinfunction "2_2") (pintype "passive"))
      (node (ref "C36") (pin "-") (pinfunction "-_-") (pintype "passive"))
      (node (ref "C37") (pin "2") (pinfunction "2_2") (pintype "passive"))
      (node (ref "C38") (pin "2") (pinfunction "2_2") (pintype "passive"))
      (node (ref "C41") (pin "1") (pinfunction "1_1") (pintype "passive"))
      (node (ref "C8") (pin "2") (pinfunction "2_2") (pintype "passive"))
      (node (ref "C9") (pin "2") (pinfunction "2_2") (pintype "passive"))
      (node (ref "D10") (pin "C") (pinfunction "C_C") (pintype "passive"))
      (node (ref "D11") (pin "C") (pinfunction "C_C") (pintype "passive"))
      (node (ref "D3") (pin "A") (pinfunction "A_A") (pintype "passive"))
      (node (ref "D4") (pin "A") (pinfunction "A_A") (pintype "passive"))
      (node (ref "D5") (pin "A") (pinfunction "A_A") (pintype "passive"))
      (node (ref "D6") (pin "A") (pinfunction "A_A") (pintype "passive"))
      (node (ref "D9") (pin "C") (pinfunction "C_C") (pintype "passive"))
      (node (ref "J1") (pin "YC") (pinfunction "C-Y_YC") (pintype "passive"))
      (node (ref "J2") (pin "1") (pinfunction "1_1") (pintype "passive"))
      (node (ref "J3") (pin "1") (pinfunction "1_1") (pintype "passive"))
      (node (ref "J4") (pin "2") (pinfunction "2_2") (pintype "passive"))
      (node (ref "J4") (pin "7") (pinfunction "7_7") (pintype "passive"))
      (node (ref "J5") (pin "10") (pinfunction "10_10") (pintype "passive"))
      (node (ref "J5") (pin "2") (pinfunction "2_2") (pintype "passive"))
      (node (ref "J5") (pin "4") (pinfunction "4_4") (pintype "passive"))
      (node (ref "J5") (pin "6") (pinfunction "6_6") (pintype "passive"))
      (node (ref "J5") (pin "8") (pinfunction "8_8") (pintype "passive"))
      (node (ref "R14") (pin "1") (pinfunction "1_1") (pintype "passive"))
      (node (ref "R15") (pin "2") (pinfunction "2_2") (pintype "passive"))
      (node (ref "R16") (pin "2") (pinfunction "2_2") (pintype "passive"))
      (node (ref "R17") (pin "2") (pinfunction "2_2") (pintype "passive"))
      (node (ref "R18") (pin "2") (pinfunction "2_2") (pintype "passive"))
      (node (ref "R25") (pin "1") (pinfunction "1_1") (pintype "passive"))
      (node (ref "R28") (pin "1") (pinfunction "1_1") (pintype "passive"))
      (node (ref "R33") (pin "1") (pinfunction "1_1") (pintype "passive"))
      (node (ref "R9") (pin "1$1") (pinfunction "1_1$1") (pintype "passive"))
      (node (ref "R9") (pin "1$2") (pinfunction "1_1$2") (pintype "passive"))
      (node (ref "S1") (pin "P$1") (pinfunction "1_P$1") (pintype "bidirectional"))
      (node (ref "U1") (pin "23") (pinfunction "VSS$1_23") (pintype "passive"))
      (node (ref "U1") (pin "35") (pinfunction "VSS$2_35") (pintype "passive"))
      (node (ref "U1") (pin "44") (pinfunction "BOOT0_44") (pintype "input"))
      (node (ref "U1") (pin "47") (pinfunction "VSS$3_47") (pintype "passive"))
      (node (ref "U1") (pin "8") (pinfunction "VSSA_8") (pintype "bidirectional"))
      (node (ref "U10") (pin "1") (pinfunction "VSS_1") (pintype "bidirectional"))
      (node (ref "U3") (pin "4") (pinfunction "GND1_4") (pintype "power_in"))
      (node (ref "U5") (pin "4") (pinfunction "GND_4") (pintype "power_in"))
      (node (ref "U6") (pin "4") (pinfunction "GND_4") (pintype "power_in"))
      (node (ref "U7") (pin "1") (pinfunction "REF_1") (pintype "power_in"))
      (node (ref "U7") (pin "2") (pinfunction "GND_2") (pintype "power_in"))
      (node (ref "U8") (pin "4") (pinfunction "GND_4") (pintype "passive"))
      (node (ref "U9") (pin "4") (pinfunction "GND_4") (pintype "passive"))
      (node (ref "X1") (pin "2") (pinfunction "2_2") (pintype "passive"))
    )
    (net (code "16") (name "GNDIO") (class "Default")
      (node (ref "C30") (pin "-") (pinfunction "-_-") (pintype "passive"))
      (node (ref "C31") (pin "2") (pinfunction "2_2") (pintype "passive"))
      (node (ref "C39") (pin "1") (pinfunction "1_1") (pintype "passive"))
      (node (ref "C40") (pin "1") (pinfunction "1_1") (pintype "passive"))
      (node (ref "J1") (pin "3") (pinfunction "3_3") (pintype "input"))
      (node (ref "J1") (pin "7") (pinfunction "7_7") (pintype "input"))
      (node (ref "J1") (pin "8") (pinfunction "8_8") (pintype "input"))
      (node (ref "J1") (pin "GC") (pinfunction "C-G_GC") (pintype "passive"))
      (node (ref "J1") (pin "M1") (pinfunction "SHIELD_M1") (pintype "passive"))
      (node (ref "J1") (pin "M2") (pinfunction "SHIELD_M2") (pintype "passive"))
      (node (ref "J6") (pin "3") (pinfunction "3_3") (pintype "passive"))
      (node (ref "J6") (pin "4") (pinfunction "4_4") (pintype "passive"))
      (node (ref "Q5") (pin "2") (pinfunction "S_2") (pintype "passive"))
      (node (ref "R35") (pin "1") (pinfunction "1_1") (pintype "passive"))
      (node (ref "U11") (pin "3") (pinfunction "GND_3") (pintype "passive"))
      (node (ref "U2") (pin "2") (pinfunction "GND_2") (pintype "power_in"))
      (node (ref "U2") (pin "8") (pinfunction "S_8") (pintype "input"))
      (node (ref "U3") (pin "5") (pinfunction "GND2_5") (pintype "power_in"))
    )
    (net (code "17") (name "IN_A") (class "Default")
      (node (ref "C26") (pin "2") (pinfunction "2_2") (pintype "passive"))
      (node (ref "R19") (pin "1") (pinfunction "1_1") (pintype "passive"))
      (node (ref "U1") (pin "12") (pinfunction "PA2_12") (pintype "bidirectional"))
    )
    (net (code "18") (name "IN_B") (class "Default")
      (node (ref "C27") (pin "2") (pinfunction "2_2") (pintype "passive"))
      (node (ref "R20") (pin "1") (pinfunction "1_1") (pintype "passive"))
      (node (ref "U1") (pin "13") (pinfunction "PA3_13") (pintype "bidirectional"))
    )
    (net (code "19") (name "IN_HI_A") (class "Default")
      (node (ref "R16") (pin "1") (pinfunction "1_1") (pintype "passive"))
      (node (ref "U1") (pin "30") (pinfunction "PA9_30") (pintype "bidirectional"))
      (node (ref "U5") (pin "2") (pinfunction "IN_HI_2") (pintype "input"))
    )
    (net (code "20") (name "IN_HI_B") (class "Default")
      (node (ref "R18") (pin "1") (pinfunction "1_1") (pintype "passive"))
      (node (ref "U1") (pin "29") (pinfunction "PA8_29") (pintype "bidirectional"))
      (node (ref "U6") (pin "2") (pinfunction "IN_HI_2") (pintype "input"))
    )
    (net (code "21") (name "IN_LO_A") (class "Default")
      (node (ref "R15") (pin "1") (pinfunction "1_1") (pintype "passive"))
      (node (ref "U1") (pin "27") (pinfunction "PB14_27") (pintype "bidirectional"))
      (node (ref "U5") (pin "3") (pinfunction "IN_LO_3") (pintype "input"))
    )
    (net (code "22") (name "IN_LO_B") (class "Default")
      (node (ref "R17") (pin "1") (pinfunction "1_1") (pintype "passive"))
      (node (ref "U1") (pin "26") (pinfunction "PB13_26") (pintype "bidirectional"))
      (node (ref "U6") (pin "3") (pinfunction "IN_LO_3") (pintype "input"))
    )
    (net (code "23") (name "ISENSE") (class "Default")
      (node (ref "C15") (pin "2") (pinfunction "2_2") (pintype "passive"))
      (node (ref "R12") (pin "1") (pinfunction "1_1") (pintype "passive"))
      (node (ref "U1") (pin "14") (pinfunction "PA4_14") (pintype "bidirectional"))
    )
    (net (code "24") (name "JMP0") (class "Default")
      (node (ref "J5") (pin "9") (pinfunction "9_9") (pintype "passive"))
      (node (ref "U1") (pin "19") (pinfunction "PB1_19") (pintype "bidirectional"))
    )
    (net (code "25") (name "JMP1") (class "Default")
      (node (ref "J5") (pin "7") (pinfunction "7_7") (pintype "passive"))
      (node (ref "U1") (pin "20") (pinfunction "PB2-BOOT1_20") (pintype "bidirectional"))
    )
    (net (code "26") (name "JMP2") (class "Default")
      (node (ref "J5") (pin "5") (pinfunction "5_5") (pintype "passive"))
      (node (ref "U1") (pin "21") (pinfunction "PB10_21") (pintype "bidirectional"))
    )
    (net (code "27") (name "JMP3") (class "Default")
      (node (ref "J5") (pin "3") (pinfunction "3_3") (pintype "passive"))
      (node (ref "U1") (pin "22") (pinfunction "PB11_22") (pintype "bidirectional"))
    )
    (net (code "28") (name "JMP4") (class "Default")
      (node (ref "J5") (pin "1") (pinfunction "1_1") (pintype "passive"))
      (node (ref "U1") (pin "25") (pinfunction "PB12_25") (pintype "bidirectional"))
    )
    (net (code "29") (name "LED0") (class "Default")
      (node (ref "R109") (pin "1") (pinfunction "1_1") (pintype "passive"))
      (node (ref "U1") (pin "16") (pinfunction "PA6_16") (pintype "bidirectional"))
    )
    (net (code "30") (name "LED1") (class "Default")
      (node (ref "R110") (pin "1") (pinfunction "1_1") (pintype "passive"))
      (node (ref "U1") (pin "17") (pinfunction "PA7_17") (pintype "bidirectional"))
    )
    (net (code "31") (name "LED2") (class "Default")
      (node (ref "R111") (pin "1") (pinfunction "1_1") (pintype "passive"))
      (node (ref "U1") (pin "18") (pinfunction "PB0_18") (pintype "bidirectional"))
    )
    (net (code "32") (name "LED_CAN") (class "Default")
      (node (ref "R31") (pin "1") (pinfunction "1_1") (pintype "passive"))
      (node (ref "U1") (pin "3") (pinfunction "PC14-OSC32_IN_3") (pintype "bidirectional"))
    )
    (net (code "33") (name "Net-(D9-PadA)") (class "Default")
      (node (ref "D9") (pin "A") (pinfunction "A_A") (pintype "passive"))
      (node (ref "R109") (pin "2") (pinfunction "2_2") (pintype "passive"))
    )
    (net (code "34") (name "Net-(D10-PadA)") (class "Default")
      (node (ref "D10") (pin "A") (pinfunction "A_A") (pintype "passive"))
      (node (ref "R110") (pin "2") (pinfunction "2_2") (pintype "passive"))
    )
    (net (code "35") (name "Net-(D11-PadA)") (class "Default")
      (node (ref "D11") (pin "A") (pinfunction "A_A") (pintype "passive"))
      (node (ref "R111") (pin "2") (pinfunction "2_2") (pintype "passive"))
    )
    (net (code "36") (name "Net-(F1-Pad2)") (class "Default")
      (node (ref "F1") (pin "2") (pinfunction "2_2") (pintype "passive"))
      (node (ref "J1") (pin "4") (pinfunction "4_4") (pintype "input"))
      (node (ref "J1") (pin "5") (pinfunction "5_5") (pintype "input"))
      (node (ref "R30") (pin "1") (pinfunction "1_1") (pintype "passive"))
    )
    (net (code "37") (name "Net-(J1-A-G)") (class "Default")
      (node (ref "J1") (pin "GA") (pinfunction "A-G_GA") (pintype "passive"))
      (node (ref "R30") (pin "2") (pinfunction "2_2") (pintype "passive"))
    )
    (net (code "38") (name "Net-(J1-A-Y)") (class "Default")
      (node (ref "J1") (pin "YA") (pinfunction "A-Y_YA") (pintype "passive"))
      (node (ref "R31") (pin "2") (pinfunction "2_2") (pintype "passive"))
    )
    (net (code "39") (name "Net-(J2-Pad3)") (class "Default")
      (node (ref "J2") (pin "3") (pinfunction "3_3") (pintype "passive"))
      (node (ref "R21") (pin "2") (pinfunction "2_2") (pintype "passive"))
    )
    (net (code "40") (name "Net-(J2-Pad4)") (class "Default")
      (node (ref "J2") (pin "4") (pinfunction "4_4") (pintype "passive"))
      (node (ref "R22") (pin "2") (pinfunction "2_2") (pintype "passive"))
    )
    (net (code "41") (name "Net-(J3-Pad3)") (class "Default")
      (node (ref "J3") (pin "3") (pinfunction "3_3") (pintype "passive"))
      (node (ref "R19") (pin "2") (pinfunction "2_2") (pintype "passive"))
    )
    (net (code "42") (name "Net-(J3-Pad4)") (class "Default")
      (node (ref "J3") (pin "4") (pinfunction "4_4") (pintype "passive"))
      (node (ref "R20") (pin "2") (pinfunction "2_2") (pintype "passive"))
    )
    (net (code "43") (name "Net-(J6-Pad2)") (class "Default")
      (node (ref "J6") (pin "2") (pinfunction "2_2") (pintype "passive"))
      (node (ref "R29") (pin "2") (pinfunction "2_2") (pintype "passive"))
    )
    (net (code "44") (name "Net-(L1-1)") (class "Default")
      (node (ref "D5") (pin "C") (pinfunction "C_C") (pintype "passive"))
      (node (ref "L1") (pin "P$1") (pinfunction "1_P$1") (pintype "passive"))
      (node (ref "U8") (pin "2") (pinfunction "SWE_2") (pintype "passive"))
    )
    (net (code "45") (name "Net-(L2-1)") (class "Default")
      (node (ref "D6") (pin "C") (pinfunction "C_C") (pintype "passive"))
      (node (ref "L2") (pin "P$1") (pinfunction "1_P$1") (pintype "passive"))
      (node (ref "U9") (pin "2") (pinfunction "SWE_2") (pintype "passive"))
    )
    (net (code "46") (name "Net-(Q1-GATE)") (class "Default")
      (node (ref "Q1") (pin "4") (pinfunction "GATE_4") (pintype "passive"))
      (node (ref "R5") (pin "2") (pinfunction "2_2") (pintype "passive"))
      (node (ref "U5") (pin "7") (pinfunction "DRV_HI_7") (pintype "output"))
    )
    (net (code "47") (name "Net-(Q2-GATE)") (class "Default")
      (node (ref "Q2") (pin "4") (pinfunction "GATE_4") (pintype "passive"))
      (node (ref "R3") (pin "2") (pinfunction "2_2") (pintype "passive"))
    )
    (net (code "48") (name "Net-(Q3-GATE)") (class "Default")
      (node (ref "Q3") (pin "4") (pinfunction "GATE_4") (pintype "passive"))
      (node (ref "R6") (pin "2") (pinfunction "2_2") (pintype "passive"))
      (node (ref "U6") (pin "7") (pinfunction "DRV_HI_7") (pintype "output"))
    )
    (net (code "49") (name "Net-(Q4-GATE)") (class "Default")
      (node (ref "Q4") (pin "4") (pinfunction "GATE_4") (pintype "passive"))
      (node (ref "R4") (pin "2") (pinfunction "2_2") (pintype "passive"))
    )
    (net (code "50") (name "Net-(Q5-D)") (class "Default")
      (node (ref "Q5") (pin "3") (pinfunction "D_3") (pintype "passive"))
      (node (ref "U4") (pin "2") (pinfunction "AC2_2") (pintype "passive"))
    )
    (net (code "51") (name "Net-(Q5-G)") (class "Default")
      (node (ref "Q5") (pin "1") (pinfunction "G_1") (pintype "passive"))
      (node (ref "R32") (pin "1") (pinfunction "1_1") (pintype "passive"))
      (node (ref "R35") (pin "2") (pinfunction "2_2") (pintype "passive"))
    )
    (net (code "52") (name "Net-(U1-OSC_IN)") (class "Default")
      (node (ref "U1") (pin "5") (pinfunction "OSC_IN_5") (pintype "input"))
      (node (ref "X1") (pin "1") (pinfunction "1_1") (pintype "passive"))
    )
    (net (code "53") (name "Net-(U1-OSC_OUT)") (class "Default")
      (node (ref "U1") (pin "6") (pinfunction "OSC_OUT_6") (pintype "output"))
      (node (ref "X1") (pin "3") (pinfunction "3_3") (pintype "passive"))
    )
    (net (code "54") (name "Net-(U2-RXD)") (class "Default")
      (node (ref "U2") (pin "4") (pinfunction "RXD_4") (pintype "output"))
      (node (ref "U3") (pin "6") (pinfunction "B2_6") (pintype "output"))
    )
    (net (code "55") (name "Net-(U2-TXD)") (class "Default")
      (node (ref "U2") (pin "1") (pinfunction "TXD_1") (pintype "input"))
      (node (ref "U3") (pin "7") (pinfunction "B1_7") (pintype "output"))
    )
    (net (code "56") (name "Net-(U4-AC1)") (class "Default")
      (node (ref "R34") (pin "1") (pinfunction "1_1") (pintype "passive"))
      (node (ref "U4") (pin "1") (pinfunction "AC1_1") (pintype "passive"))
    )
    (net (code "57") (name "Net-(U5-BRIDGE)") (class "Default")
      (node (ref "C10") (pin "2") (pinfunction "2_2") (pintype "passive"))
      (node (ref "D3") (pin "C") (pinfunction "C_C") (pintype "passive"))
      (node (ref "R1") (pin "1") (pinfunction "1_1") (pintype "passive"))
      (node (ref "U5") (pin "6") (pinfunction "BRIDGE_6") (pintype "power_in"))
    )
    (net (code "58") (name "Net-(U5-DRV_LO)") (class "Default")
      (node (ref "R3") (pin "1") (pinfunction "1_1") (pintype "passive"))
      (node (ref "R7") (pin "2") (pinfunction "2_2") (pintype "passive"))
      (node (ref "U5") (pin "5") (pinfunction "DRV_LO_5") (pintype "output"))
    )
    (net (code "59") (name "Net-(U5-VBOOT)") (class "Default")
      (node (ref "C10") (pin "1") (pinfunction "1_1") (pintype "passive"))
      (node (ref "D1") (pin "C") (pinfunction "C_C") (pintype "passive"))
      (node (ref "U5") (pin "8") (pinfunction "VBOOT_8") (pintype "power_in"))
    )
    (net (code "60") (name "Net-(U6-BRIDGE)") (class "Default")
      (node (ref "C11") (pin "2") (pinfunction "2_2") (pintype "passive"))
      (node (ref "D4") (pin "C") (pinfunction "C_C") (pintype "passive"))
      (node (ref "R2") (pin "1") (pinfunction "1_1") (pintype "passive"))
      (node (ref "U6") (pin "6") (pinfunction "BRIDGE_6") (pintype "power_in"))
    )
    (net (code "61") (name "Net-(U6-DRV_LO)") (class "Default")
      (node (ref "R4") (pin "1") (pinfunction "1_1") (pintype "passive"))
      (node (ref "R8") (pin "2") (pinfunction "2_2") (pintype "passive"))
      (node (ref "U6") (pin "5") (pinfunction "DRV_LO_5") (pintype "output"))
    )
    (net (code "62") (name "Net-(U6-VBOOT)") (class "Default")
      (node (ref "C11") (pin "1") (pinfunction "1_1") (pintype "passive"))
      (node (ref "D2") (pin "C") (pinfunction "C_C") (pintype "passive"))
      (node (ref "U6") (pin "8") (pinfunction "VBOOT_8") (pintype "power_in"))
    )
    (net (code "63") (name "Net-(U7-IN+)") (class "Default")
      (node (ref "C13") (pin "2") (pinfunction "2_2") (pintype "passive"))
      (node (ref "R10") (pin "2") (pinfunction "2_2") (pintype "passive"))
      (node (ref "U7") (pin "4") (pinfunction "IN+_4") (pintype "passive"))
    )
    (net (code "64") (name "Net-(U7-IN-)") (class "Default")
      (node (ref "C13") (pin "1") (pinfunction "1_1") (pintype "passive"))
      (node (ref "R11") (pin "2") (pinfunction "2_2") (pintype "passive"))
      (node (ref "U7") (pin "5") (pinfunction "IN-_5") (pintype "passive"))
    )
    (net (code "65") (name "Net-(U7-OUT)") (class "Default")
      (node (ref "R12") (pin "2") (pinfunction "2_2") (pintype "passive"))
      (node (ref "U7") (pin "6") (pinfunction "OUT_6") (pintype "passive"))
    )
    (net (code "66") (name "Net-(U8-DC)") (class "Default")
      (node (ref "R23") (pin "2") (pinfunction "2_2") (pintype "passive"))
      (node (ref "U8") (pin "1") (pinfunction "SWC_1") (pintype "passive"))
      (node (ref "U8") (pin "7") (pinfunction "IS_7") (pintype "passive"))
      (node (ref "U8") (pin "8") (pinfunction "DC_8") (pintype "passive"))
    )
    (net (code "67") (name "Net-(U8-FB)") (class "Default")
      (node (ref "R24") (pin "1") (pinfunction "1_1") (pintype "passive"))
      (node (ref "R25") (pin "2") (pinfunction "2_2") (pintype "passive"))
      (node (ref "U8") (pin "5") (pinfunction "FB_5") (pintype "passive"))
    )
    (net (code "68") (name "Net-(U8-TC)") (class "Default")
      (node (ref "C34") (pin "1") (pinfunction "1_1") (pintype "passive"))
      (node (ref "U8") (pin "3") (pinfunction "TC_3") (pintype "passive"))
    )
    (net (code "69") (name "Net-(U9-DC)") (class "Default")
      (node (ref "R26") (pin "2") (pinfunction "2_2") (pintype "passive"))
      (node (ref "U9") (pin "1") (pinfunction "SWC_1") (pintype "passive"))
      (node (ref "U9") (pin "7") (pinfunction "IS_7") (pintype "passive"))
      (node (ref "U9") (pin "8") (pinfunction "DC_8") (pintype "passive"))
    )
    (net (code "70") (name "Net-(U9-FB)") (class "Default")
      (node (ref "R27") (pin "1") (pinfunction "1_1") (pintype "passive"))
      (node (ref "R28") (pin "2") (pinfunction "2_2") (pintype "passive"))
      (node (ref "U9") (pin "5") (pinfunction "FB_5") (pintype "passive"))
    )
    (net (code "71") (name "Net-(U9-TC)") (class "Default")
      (node (ref "C35") (pin "1") (pinfunction "1_1") (pintype "passive"))
      (node (ref "U9") (pin "3") (pinfunction "TC_3") (pintype "passive"))
    )
    (net (code "72") (name "SWCLK") (class "Default")
      (node (ref "J4") (pin "4") (pinfunction "4_4") (pintype "passive"))
      (node (ref "U1") (pin "37") (pinfunction "PA14-JTCK-SWCLK_37") (pintype "bidirectional"))
    )
    (net (code "73") (name "SWDIO") (class "Default")
      (node (ref "J4") (pin "6") (pinfunction "6_6") (pintype "passive"))
      (node (ref "U1") (pin "34") (pinfunction "PA13-JTMS-SWDIO_34") (pintype "bidirectional"))
    )
    (net (code "74") (name "UART_RX") (class "Default")
      (node (ref "J4") (pin "1") (pinfunction "1_1") (pintype "passive"))
      (node (ref "U1") (pin "43") (pinfunction "PB7_43") (pintype "bidirectional"))
    )
    (net (code "75") (name "UART_TX") (class "Default")
      (node (ref "J4") (pin "3") (pinfunction "3_3") (pintype "passive"))
      (node (ref "U1") (pin "42") (pinfunction "PB6_42") (pintype "bidirectional"))
    )
    (net (code "76") (name "VCC") (class "Default")
      (node (ref "C1") (pin "+") (pinfunction "+_+") (pintype "passive"))
      (node (ref "C2") (pin "+") (pinfunction "+_+") (pintype "passive"))
      (node (ref "C3") (pin "1") (pinfunction "1_1") (pintype "passive"))
      (node (ref "C32") (pin "+") (pinfunction "+_+") (pintype "passive"))
      (node (ref "C33") (pin "+") (pinfunction "+_+") (pintype "passive"))
      (node (ref "C4") (pin "1") (pinfunction "1_1") (pintype "passive"))
      (node (ref "C5") (pin "1") (pinfunction "1_1") (pintype "passive"))
      (node (ref "C6") (pin "1") (pinfunction "1_1") (pintype "passive"))
      (node (ref "C7") (pin "1") (pinfunction "1_1") (pintype "passive"))
      (node (ref "Q1") (pin "5") (pinfunction "DRAIN_5") (pintype "passive"))
      (node (ref "Q3") (pin "5") (pinfunction "DRAIN_5") (pintype "passive"))
      (node (ref "R13") (pin "2") (pinfunction "2_2") (pintype "passive"))
      (node (ref "R23") (pin "1") (pinfunction "1_1") (pintype "passive"))
      (node (ref "R26") (pin "1") (pinfunction "1_1") (pintype "passive"))
      (node (ref "U8") (pin "6") (pinfunction "VCC_6") (pintype "passive"))
      (node (ref "U9") (pin "6") (pinfunction "VCC_6") (pintype "passive"))
    )
    (net (code "77") (name "VCS") (class "Default")
      (node (ref "C12") (pin "2") (pinfunction "2_2") (pintype "passive"))
      (node (ref "C4") (pin "2") (pinfunction "2_2") (pintype "passive"))
      (node (ref "C5") (pin "2") (pinfunction "2_2") (pintype "passive"))
      (node (ref "C6") (pin "2") (pinfunction "2_2") (pintype "passive"))
      (node (ref "C7") (pin "2") (pinfunction "2_2") (pintype "passive"))
      (node (ref "Q2") (pin "1") (pinfunction "SOURCE_1") (pintype "passive"))
      (node (ref "Q2") (pin "2") (pinfunction "SOURCE_2") (pintype "passive"))
      (node (ref "Q2") (pin "3") (pinfunction "SOURCE_3") (pintype "passive"))
      (node (ref "Q4") (pin "1") (pinfunction "SOURCE_1") (pintype "passive"))
      (node (ref "Q4") (pin "2") (pinfunction "SOURCE_2") (pintype "passive"))
      (node (ref "Q4") (pin "3") (pinfunction "SOURCE_3") (pintype "passive"))
      (node (ref "R7") (pin "1") (pinfunction "1_1") (pintype "passive"))
      (node (ref "R8") (pin "1") (pinfunction "1_1") (pintype "passive"))
      (node (ref "R9") (pin "2$1") (pinfunction "2_2$1") (pintype "passive"))
      (node (ref "R9") (pin "2$2") (pinfunction "2_2$2") (pintype "passive"))
    )
    (net (code "78") (name "VCS_B_N") (class "Default")
      (node (ref "R11") (pin "1") (pinfunction "1_1") (pintype "passive"))
      (node (ref "R9") (pin "1S") (pinfunction "1S_1S") (pintype "passive"))
    )
    (net (code "79") (name "VCS_B_P") (class "Default")
      (node (ref "R10") (pin "1") (pinfunction "1_1") (pintype "passive"))
      (node (ref "R9") (pin "2S") (pinfunction "2S_2S") (pintype "passive"))
    )
    (net (code "80") (name "VSENSE") (class "Default")
      (node (ref "C16") (pin "2") (pinfunction "2_2") (pintype "passive"))
      (node (ref "R13") (pin "1") (pinfunction "1_1") (pintype "passive"))
      (node (ref "R14") (pin "2") (pinfunction "2_2") (pintype "passive"))
      (node (ref "U1") (pin "15") (pinfunction "PA5_15") (pintype "bidirectional"))
    )
    (net (code "81") (name "unconnected-(U1-PA10-Pad31)") (class "Default")
      (node (ref "U1") (pin "31") (pinfunction "PA10_31") (pintype "bidirectional"))
    )
    (net (code "82") (name "unconnected-(U1-PA11-Pad32)") (class "Default")
      (node (ref "U1") (pin "32") (pinfunction "PA11_32") (pintype "bidirectional"))
    )
    (net (code "83") (name "unconnected-(U1-PA12-Pad33)") (class "Default")
      (node (ref "U1") (pin "33") (pinfunction "PA12_33") (pintype "bidirectional"))
    )
    (net (code "84") (name "unconnected-(U1-PA15-JTDI-Pad38)") (class "Default")
      (node (ref "U1") (pin "38") (pinfunction "PA15-JTDI_38") (pintype "bidirectional"))
    )
    (net (code "85") (name "unconnected-(U1-PB3-JTDO-Pad39)") (class "Default")
      (node (ref "U1") (pin "39") (pinfunction "PB3-JTDO_39") (pintype "bidirectional"))
    )
    (net (code "86") (name "unconnected-(U1-PB4-JNTRST-Pad40)") (class "Default")
      (node (ref "U1") (pin "40") (pinfunction "PB4-JNTRST_40") (pintype "bidirectional"))
    )
    (net (code "87") (name "unconnected-(U1-PB5-Pad41)") (class "Default")
      (node (ref "U1") (pin "41") (pinfunction "PB5_41") (pintype "bidirectional"))
    )
    (net (code "88") (name "unconnected-(U1-PB15-Pad28)") (class "Default")
      (node (ref "U1") (pin "28") (pinfunction "PB15_28") (pintype "bidirectional"))
    )
    (net (code "89") (name "unconnected-(U1-PC15-OSC32_OUT-Pad4)") (class "Default")
      (node (ref "U1") (pin "4") (pinfunction "PC15-OSC32_OUT_4") (pintype "bidirectional"))
    )
    (net (code "90") (name "unconnected-(U1-VBAT-Pad1)") (class "Default")
      (node (ref "U1") (pin "1") (pinfunction "VBAT_1") (pintype "passive"))
    )
    (net (code "91") (name "~{EMS_ISO}") (class "Default")
      (node (ref "J1") (pin "6") (pinfunction "6_6") (pintype "input"))
      (node (ref "R32") (pin "2") (pinfunction "2_2") (pintype "passive"))
    )
    (net (code "92") (name "~{EMS}") (class "Default")
      (node (ref "R33") (pin "2") (pinfunction "2_2") (pintype "passive"))
      (node (ref "U1") (pin "2") (pinfunction "PC13-TAMPER-RTC_2") (pintype "bidirectional"))
      (node (ref "U4") (pin "3") (pinfunction "E_3") (pintype "passive"))
    )
    (net (code "93") (name "~{RESET}") (class "Default")
      (node (ref "C19") (pin "2") (pinfunction "2_2") (pintype "passive"))
      (node (ref "S1") (pin "P$2") (pinfunction "2_P$2") (pintype "bidirectional"))
      (node (ref "U1") (pin "7") (pinfunction "NRST_7") (pintype "bidirectional"))
    )
  )
)
